# BV100011_DEBUG.net
KiCad netlist of a schematic drawn in Altium Designer
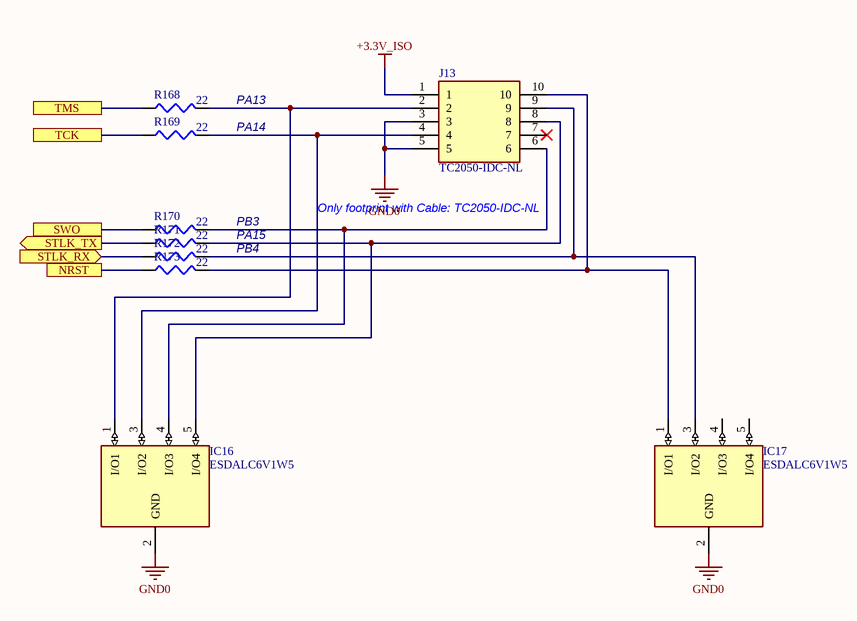
[diagram p0: BV100011_DEBUG.SchDoc]

(export (version "E")
  (design (tool "Eeschema 10.0.6"))
  (components
    (comp (ref "IC16")
      (value "ESDALC6V1W5")
      (footprint "SOT65P210X110-5N")
      (description "Integrated Circuit")
      (fields
        (field (name "MOUSER PART NUMBER") "511-ESDALC6V1W5")
        (field (name "RS PART NUMBER") "0250044P")
      )
      (libsource (lib "SamacSys") (part "ESDALC6V1W5"))
    )
    (comp (ref "IC17")
      (value "ESDALC6V1W5")
      (footprint "SOT65P210X110-5N")
      (description "Integrated Circuit")
      (fields
        (field (name "MOUSER PART NUMBER") "511-ESDALC6V1W5")
        (field (name "RS PART NUMBER") "0250044P")
      )
      (libsource (lib "SamacSys") (part "ESDALC6V1W5"))
    )
    (comp (ref "J13")
      (value "TC2050-IDC-NL")
      (footprint "CON_TAG-C_TC2050-IDC-NL")
      (description "Plug-Of-Nailsâ„¢ Adapter Cable")
      (fields (field (name "MF") "Tag-Connect LLC"))
      (libsource (lib "TC2050-IDC-NL") (part "TC2050-IDC-NL"))
    )
    (comp (ref "R168")
      (value "22")
      (footprint "J1-0603")
      (description "Resistor")
      (fields (field (name "PUBLISHER") "Altium Limited"))
      (libsource (lib "Miscellaneous Devices") (part "Res3"))
    )
    (comp (ref "R169")
      (value "22")
      (footprint "J1-0603")
      (description "Resistor")
      (fields (field (name "PUBLISHER") "Altium Limited"))
      (libsource (lib "Miscellaneous Devices") (part "Res3"))
    )
    (comp (ref "R170")
      (value "22")
      (footprint "J1-0603")
      (description "Resistor")
      (fields (field (name "PUBLISHER") "Altium Limited"))
      (libsource (lib "Miscellaneous Devices") (part "Res3"))
    )
    (comp (ref "R171")
      (value "22")
      (footprint "J1-0603")
      (description "Resistor")
      (fields (field (name "PUBLISHER") "Altium Limited"))
      (libsource (lib "Miscellaneous Devices") (part "Res3"))
    )
    (comp (ref "R172")
      (value "22")
      (footprint "J1-0603")
      (description "Resistor")
      (fields (field (name "PUBLISHER") "Altium Limited"))
      (libsource (lib "Miscellaneous Devices") (part "Res3"))
    )
    (comp (ref "R173")
      (value "22")
      (footprint "J1-0603")
      (description "Resistor")
      (fields (field (name "PUBLISHER") "Altium Limited"))
      (libsource (lib "Miscellaneous Devices") (part "Res3"))
    )
  )
  (nets
    (net (code "1") (name "+3.3V_ISO") (class "Default")
      (node (ref "J13") (pin "1") (pinfunction "1_1") (pintype "passive"))
    )
    (net (code "2") (name "/NRST") (class "Default")
      (node (ref "R173") (pin "1") (pinfunction "1_1") (pintype "passive"))
    )
    (net (code "3") (name "/STLK_RX") (class "Default")
      (node (ref "R172") (pin "1") (pinfunction "1_1") (pintype "passive"))
    )
    (net (code "4") (name "/STLK_TX") (class "Default")
      (node (ref "R171") (pin "1") (pinfunction "1_1") (pintype "passive"))
    )
    (net (code "5") (name "/SWO") (class "Default")
      (node (ref "R170") (pin "1") (pinfunction "1_1") (pintype "passive"))
    )
    (net (code "6") (name "/TCK") (class "Default")
      (node (ref "R169") (pin "1") (pinfunction "1_1") (pintype "passive"))
    )
    (net (code "7") (name "/TMS") (class "Default")
      (node (ref "R168") (pin "1") (pinfunction "1_1") (pintype "passive"))
    )
    (net (code "8") (name "GND0") (class "Default")
      (node (ref "IC16") (pin "2") (pinfunction "GND_2") (pintype "power_in"))
      (node (ref "IC17") (pin "2") (pinfunction "GND_2") (pintype "power_in"))
      (node (ref "J13") (pin "3") (pinfunction "3_3") (pintype "passive"))
      (node (ref "J13") (pin "5") (pinfunction "5_5") (pintype "passive"))
    )
    (net (code "9") (name "Net-(IC16-I{slash}O1)") (class "Default")
      (node (ref "IC16") (pin "1") (pinfunction "I/O1_1") (pintype "bidirectional"))
      (node (ref "J13") (pin "2") (pinfunction "2_2") (pintype "passive"))
      (node (ref "R168") (pin "2") (pinfunction "2_2") (pintype "passive"))
    )
    (net (code "10") (name "Net-(IC16-I{slash}O2)") (class "Default")
      (node (ref "IC16") (pin "3") (pinfunction "I/O2_3") (pintype "bidirectional"))
      (node (ref "J13") (pin "4") (pinfunction "4_4") (pintype "passive"))
      (node (ref "R169") (pin "2") (pinfunction "2_2") (pintype "passive"))
    )
    (net (code "11") (name "Net-(IC16-I{slash}O3)") (class "Default")
      (node (ref "IC16") (pin "4") (pinfunction "I/O3_4") (pintype "bidirectional"))
      (node (ref "J13") (pin "6") (pinfunction "6_6") (pintype "passive"))
      (node (ref "R170") (pin "2") (pinfunction "2_2") (pintype "passive"))
    )
    (net (code "12") (name "Net-(IC16-I{slash}O4)") (class "Default")
      (node (ref "IC16") (pin "5") (pinfunction "I/O4_5") (pintype "bidirectional"))
      (node (ref "J13") (pin "8") (pinfunction "8_8") (pintype "passive"))
      (node (ref "R171") (pin "2") (pinfunction "2_2") (pintype "passive"))
    )
    (net (code "13") (name "Net-(IC17-I{slash}O1)") (class "Default")
      (node (ref "IC17") (pin "1") (pinfunction "I/O1_1") (pintype "bidirectional"))
      (node (ref "J13") (pin "10") (pinfunction "10_10") (pintype "passive"))
      (node (ref "R173") (pin "2") (pinfunction "2_2") (pintype "passive"))
    )
    (net (code "14") (name "Net-(IC17-I{slash}O2)") (class "Default")
      (node (ref "IC17") (pin "3") (pinfunction "I/O2_3") (pintype "bidirectional"))
      (node (ref "J13") (pin "9") (pinfunction "9_9") (pintype "passive"))
      (node (ref "R172") (pin "2") (pinfunction "2_2") (pintype "passive"))
    )
    (net (code "15") (name "unconnected-(IC17-I{slash}O3-Pad4)") (class "Default")
      (node (ref "IC17") (pin "4") (pinfunction "I/O3_4") (pintype "bidirectional"))
    )
    (net (code "16") (name "unconnected-(IC17-I{slash}O4-Pad5)") (class "Default")
      (node (ref "IC17") (pin "5") (pinfunction "I/O4_5") (pintype "bidirectional"))
    )
    (net (code "17") (name "unconnected-(J13-Pad7)") (class "Default")
      (node (ref "J13") (pin "7") (pinfunction "7_7") (pintype "passive+no_connect"))
    )
  )
)
